# UnitedRefrigerator.net
KiCad netlist of a schematic drawn in EAGLE
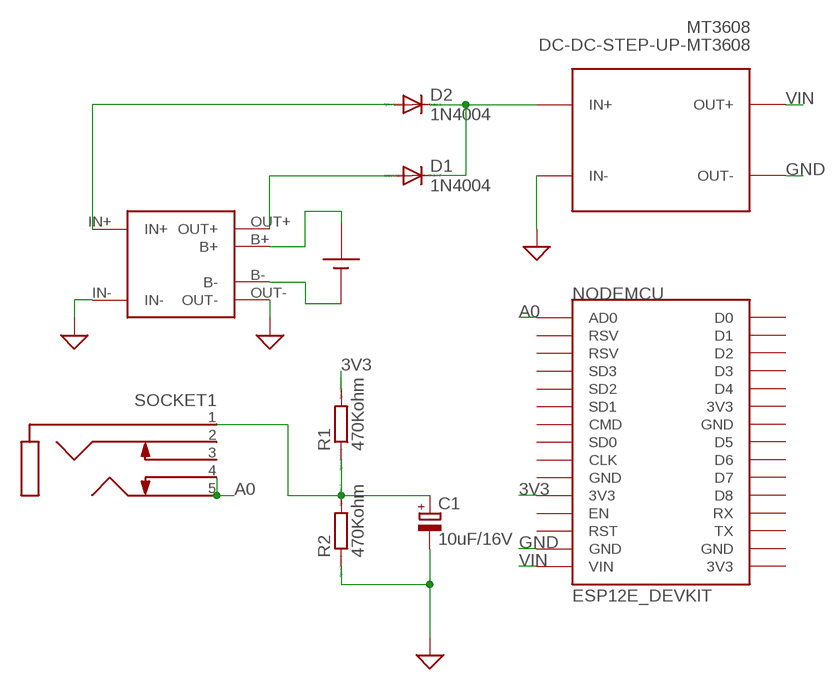
[diagram p0: schematic, sheet 1]

(export (version "E")
  (design (tool "Eeschema 10.0.6"))
  (components
    (comp (ref "C1")
      (value "10uF/16V")
      (footprint "eagle-import:E2,5-6")
      (libsource (lib "eagle-import") (part "CPOL-EUE2.5-6"))
    )
    (comp (ref "D1")
      (value "1N4004")
      (footprint "eagle-import:DO41-10")
      (libsource (lib "eagle-import") (part "1N4004"))
    )
    (comp (ref "D2")
      (value "1N4004")
      (footprint "eagle-import:DO41-10")
      (libsource (lib "eagle-import") (part "1N4004"))
    )
    (comp (ref "MT3608")
      (value "DC-DC-STEP-UP-MT3608")
      (footprint "eagle-import:DC-DC-STEP-UP-MT3608")
      (libsource (lib "eagle-import") (part "DC-DC-STEP-UP-MT3608"))
    )
    (comp (ref "NODEMCU")
      (value "ESP12E_DEVKIT")
      (footprint "eagle-import:ESP12E_DEVKIT")
      (libsource (lib "eagle-import") (part "ESP12E_DEVKIT"))
    )
    (comp (ref "R1")
      (value "470Kohm")
      (footprint "eagle-import:0204_7")
      (libsource (lib "eagle-import") (part "R0204/7"))
    )
    (comp (ref "R2")
      (value "470Kohm")
      (footprint "eagle-import:0204_7")
      (libsource (lib "eagle-import") (part "R0204/7"))
    )
    (comp (ref "SOCKET1")
      (value "STEREO_JACK3F07")
      (footprint "eagle-import:3.5AUDIO_3F07")
      (libsource (lib "eagle-import") (part "STEREO_JACK3F07"))
    )
    (comp (ref "TP4056")
      (value "TP4056-MODULE")
      (footprint "eagle-import:TP4056-LITHIUM-PROTECTED-MODULE")
      (libsource (lib "eagle-import") (part "TP4056-MODULE"))
    )
    (comp (ref "U$3")
      (value "18650CABLE")
      (footprint "eagle-import:18650-CASE-CABLE")
      (libsource (lib "eagle-import") (part "18650CABLE"))
    )
  )
  (nets
    (net (code "1") (name "/3V3") (class "Default")
      (node (ref "NODEMCU") (pin "3V3@0") (pinfunction "3V3_3V3@0") (pintype "bidirectional"))
      (node (ref "R1") (pin "2") (pinfunction "2_2") (pintype "passive"))
    )
    (net (code "2") (name "/A0") (class "Default")
      (node (ref "NODEMCU") (pin "AD0") (pinfunction "AD0_AD0") (pintype "bidirectional"))
      (node (ref "SOCKET1") (pin "4") (pinfunction "RSWITCH_4") (pintype "bidirectional"))
      (node (ref "SOCKET1") (pin "5") (pinfunction "RING_5") (pintype "bidirectional"))
    )
    (net (code "3") (name "/VIN") (class "Default")
      (node (ref "MT3608") (pin "OUT+") (pinfunction "OUT+_OUT+") (pintype "bidirectional"))
      (node (ref "NODEMCU") (pin "VIN") (pinfunction "VIN_VIN") (pintype "bidirectional"))
    )
    (net (code "4") (name "Net-(D1-PadA)") (class "Default")
      (node (ref "D1") (pin "A") (pinfunction "A_A") (pintype "passive"))
      (node (ref "TP4056") (pin "OUT+") (pinfunction "OUT+_OUT+") (pintype "power_in"))
    )
    (net (code "5") (name "Net-(D1-PadC)") (class "Default")
      (node (ref "D1") (pin "C") (pinfunction "C_C") (pintype "passive"))
      (node (ref "D2") (pin "C") (pinfunction "C_C") (pintype "passive"))
      (node (ref "MT3608") (pin "IN+") (pinfunction "IN+_IN+") (pintype "bidirectional"))
    )
    (net (code "6") (name "Net-(D2-PadA)") (class "Default")
      (node (ref "D2") (pin "A") (pinfunction "A_A") (pintype "passive"))
      (node (ref "TP4056") (pin "IN+") (pinfunction "IN+_IN+") (pintype "power_in"))
    )
    (net (code "7") (name "Net-(SOCKET1-SLEEVE)") (class "Default")
      (node (ref "C1") (pin "+") (pinfunction "+_+") (pintype "passive"))
      (node (ref "R1") (pin "1") (pinfunction "1_1") (pintype "passive"))
      (node (ref "R2") (pin "2") (pinfunction "2_2") (pintype "passive"))
      (node (ref "SOCKET1") (pin "1") (pinfunction "SLEEVE_1") (pintype "bidirectional"))
    )
    (net (code "8") (name "Net-(TP4056-PadB+)") (class "Default")
      (node (ref "TP4056") (pin "B+") (pinfunction "B+_B+") (pintype "power_in"))
      (node (ref "U$3") (pin "POS") (pinfunction "POS_POS") (pintype "power_in"))
    )
    (net (code "9") (name "Net-(TP4056-PadB-)") (class "Default")
      (node (ref "TP4056") (pin "B-") (pinfunction "B-_B-") (pintype "power_in"))
      (node (ref "U$3") (pin "NEG") (pinfunction "NEG_NEG") (pintype "power_in"))
    )
    (net (code "10") (name "SUP") (class "Default")
      (node (ref "C1") (pin "-") (pinfunction "-_-") (pintype "passive"))
      (node (ref "MT3608") (pin "IN-") (pinfunction "IN-_IN-") (pintype "bidirectional"))
      (node (ref "MT3608") (pin "OUT-") (pinfunction "OUT-_OUT-") (pintype "bidirectional"))
      (node (ref "NODEMCU") (pin "GND@1") (pinfunction "GND_GND@1") (pintype "bidirectional"))
      (node (ref "R2") (pin "1") (pinfunction "1_1") (pintype "passive"))
      (node (ref "TP4056") (pin "IN-") (pinfunction "IN-_IN-") (pintype "power_in"))
      (node (ref "TP4056") (pin "OUT-") (pinfunction "OUT-_OUT-") (pintype "power_in"))
    )
    (net (code "11") (name "unconnected-(NODEMCU-3V3-Pad3V3@1)") (class "Default")
      (node (ref "NODEMCU") (pin "3V3@1") (pinfunction "3V3_3V3@1") (pintype "bidirectional"))
    )
    (net (code "12") (name "unconnected-(NODEMCU-3V3-Pad3V3@2)") (class "Default")
      (node (ref "NODEMCU") (pin "3V3@2") (pinfunction "3V3_3V3@2") (pintype "bidirectional"))
    )
    (net (code "13") (name "unconnected-(NODEMCU-GND-PadGND@0)") (class "Default")
      (node (ref "NODEMCU") (pin "GND@0") (pinfunction "GND_GND@0") (pintype "bidirectional"))
    )
    (net (code "14") (name "unconnected-(NODEMCU-GND-PadGND@2)") (class "Default")
      (node (ref "NODEMCU") (pin "GND@2") (pinfunction "GND_GND@2") (pintype "bidirectional"))
    )
    (net (code "15") (name "unconnected-(NODEMCU-GND-PadGND@3)") (class "Default")
      (node (ref "NODEMCU") (pin "GND@3") (pinfunction "GND_GND@3") (pintype "bidirectional"))
    )
    (net (code "16") (name "unconnected-(NODEMCU-PadCLK)") (class "Default")
      (node (ref "NODEMCU") (pin "CLK") (pinfunction "CLK_CLK") (pintype "bidirectional"))
    )
    (net (code "17") (name "unconnected-(NODEMCU-PadCMD)") (class "Default")
      (node (ref "NODEMCU") (pin "CMD") (pinfunction "CMD_CMD") (pintype "bidirectional"))
    )
    (net (code "18") (name "unconnected-(NODEMCU-PadD0)") (class "Default")
      (node (ref "NODEMCU") (pin "D0") (pinfunction "D0_D0") (pintype "bidirectional"))
    )
    (net (code "19") (name "unconnected-(NODEMCU-PadD1)") (class "Default")
      (node (ref "NODEMCU") (pin "D1") (pinfunction "D1_D1") (pintype "bidirectional"))
    )
    (net (code "20") (name "unconnected-(NODEMCU-PadD2)") (class "Default")
      (node (ref "NODEMCU") (pin "D2") (pinfunction "D2_D2") (pintype "bidirectional"))
    )
    (net (code "21") (name "unconnected-(NODEMCU-PadD3)") (class "Default")
      (node (ref "NODEMCU") (pin "D3") (pinfunction "D3_D3") (pintype "bidirectional"))
    )
    (net (code "22") (name "unconnected-(NODEMCU-PadD4)") (class "Default")
      (node (ref "NODEMCU") (pin "D4") (pinfunction "D4_D4") (pintype "bidirectional"))
    )
    (net (code "23") (name "unconnected-(NODEMCU-PadD5)") (class "Default")
      (node (ref "NODEMCU") (pin "D5") (pinfunction "D5_D5") (pintype "bidirectional"))
    )
    (net (code "24") (name "unconnected-(NODEMCU-PadD6)") (class "Default")
      (node (ref "NODEMCU") (pin "D6") (pinfunction "D6_D6") (pintype "bidirectional"))
    )
    (net (code "25") (name "unconnected-(NODEMCU-PadD7)") (class "Default")
      (node (ref "NODEMCU") (pin "D7") (pinfunction "D7_D7") (pintype "bidirectional"))
    )
    (net (code "26") (name "unconnected-(NODEMCU-PadD8)") (class "Default")
      (node (ref "NODEMCU") (pin "D8") (pinfunction "D8_D8") (pintype "bidirectional"))
    )
    (net (code "27") (name "unconnected-(NODEMCU-PadEN)") (class "Default")
      (node (ref "NODEMCU") (pin "EN") (pinfunction "EN_EN") (pintype "bidirectional"))
    )
    (net (code "28") (name "unconnected-(NODEMCU-PadRST)") (class "Default")
      (node (ref "NODEMCU") (pin "RST") (pinfunction "RST_RST") (pintype "bidirectional"))
    )
    (net (code "29") (name "unconnected-(NODEMCU-PadRX)") (class "Default")
      (node (ref "NODEMCU") (pin "RX") (pinfunction "RX_RX") (pintype "bidirectional"))
    )
    (net (code "30") (name "unconnected-(NODEMCU-PadSD0)") (class "Default")
      (node (ref "NODEMCU") (pin "SD0") (pinfunction "SD0_SD0") (pintype "bidirectional"))
    )
    (net (code "31") (name "unconnected-(NODEMCU-PadSD1)") (class "Default")
      (node (ref "NODEMCU") (pin "SD1") (pinfunction "SD1_SD1") (pintype "bidirectional"))
    )
    (net (code "32") (name "unconnected-(NODEMCU-PadSD2)") (class "Default")
      (node (ref "NODEMCU") (pin "SD2") (pinfunction "SD2_SD2") (pintype "bidirectional"))
    )
    (net (code "33") (name "unconnected-(NODEMCU-PadSD3)") (class "Default")
      (node (ref "NODEMCU") (pin "SD3") (pinfunction "SD3_SD3") (pintype "bidirectional"))
    )
    (net (code "34") (name "unconnected-(NODEMCU-PadTX)") (class "Default")
      (node (ref "NODEMCU") (pin "TX") (pinfunction "TX_TX") (pintype "bidirectional"))
    )
    (net (code "35") (name "unconnected-(NODEMCU-RSV-PadRSV@0)") (class "Default")
      (node (ref "NODEMCU") (pin "RSV@0") (pinfunction "RSV_RSV@0") (pintype "bidirectional"))
    )
    (net (code "36") (name "unconnected-(NODEMCU-RSV-PadRSV@1)") (class "Default")
      (node (ref "NODEMCU") (pin "RSV@1") (pinfunction "RSV_RSV@1") (pintype "bidirectional"))
    )
    (net (code "37") (name "unconnected-(SOCKET1-TIP-Pad2)") (class "Default")
      (node (ref "SOCKET1") (pin "2") (pinfunction "TIP_2") (pintype "bidirectional"))
    )
    (net (code "38") (name "unconnected-(SOCKET1-TSWITCH-Pad3)") (class "Default")
      (node (ref "SOCKET1") (pin "3") (pinfunction "TSWITCH_3") (pintype "bidirectional"))
    )
  )
)
